# T1_Card_Top.net
KiCad netlist of a schematic drawn in Altium Designer
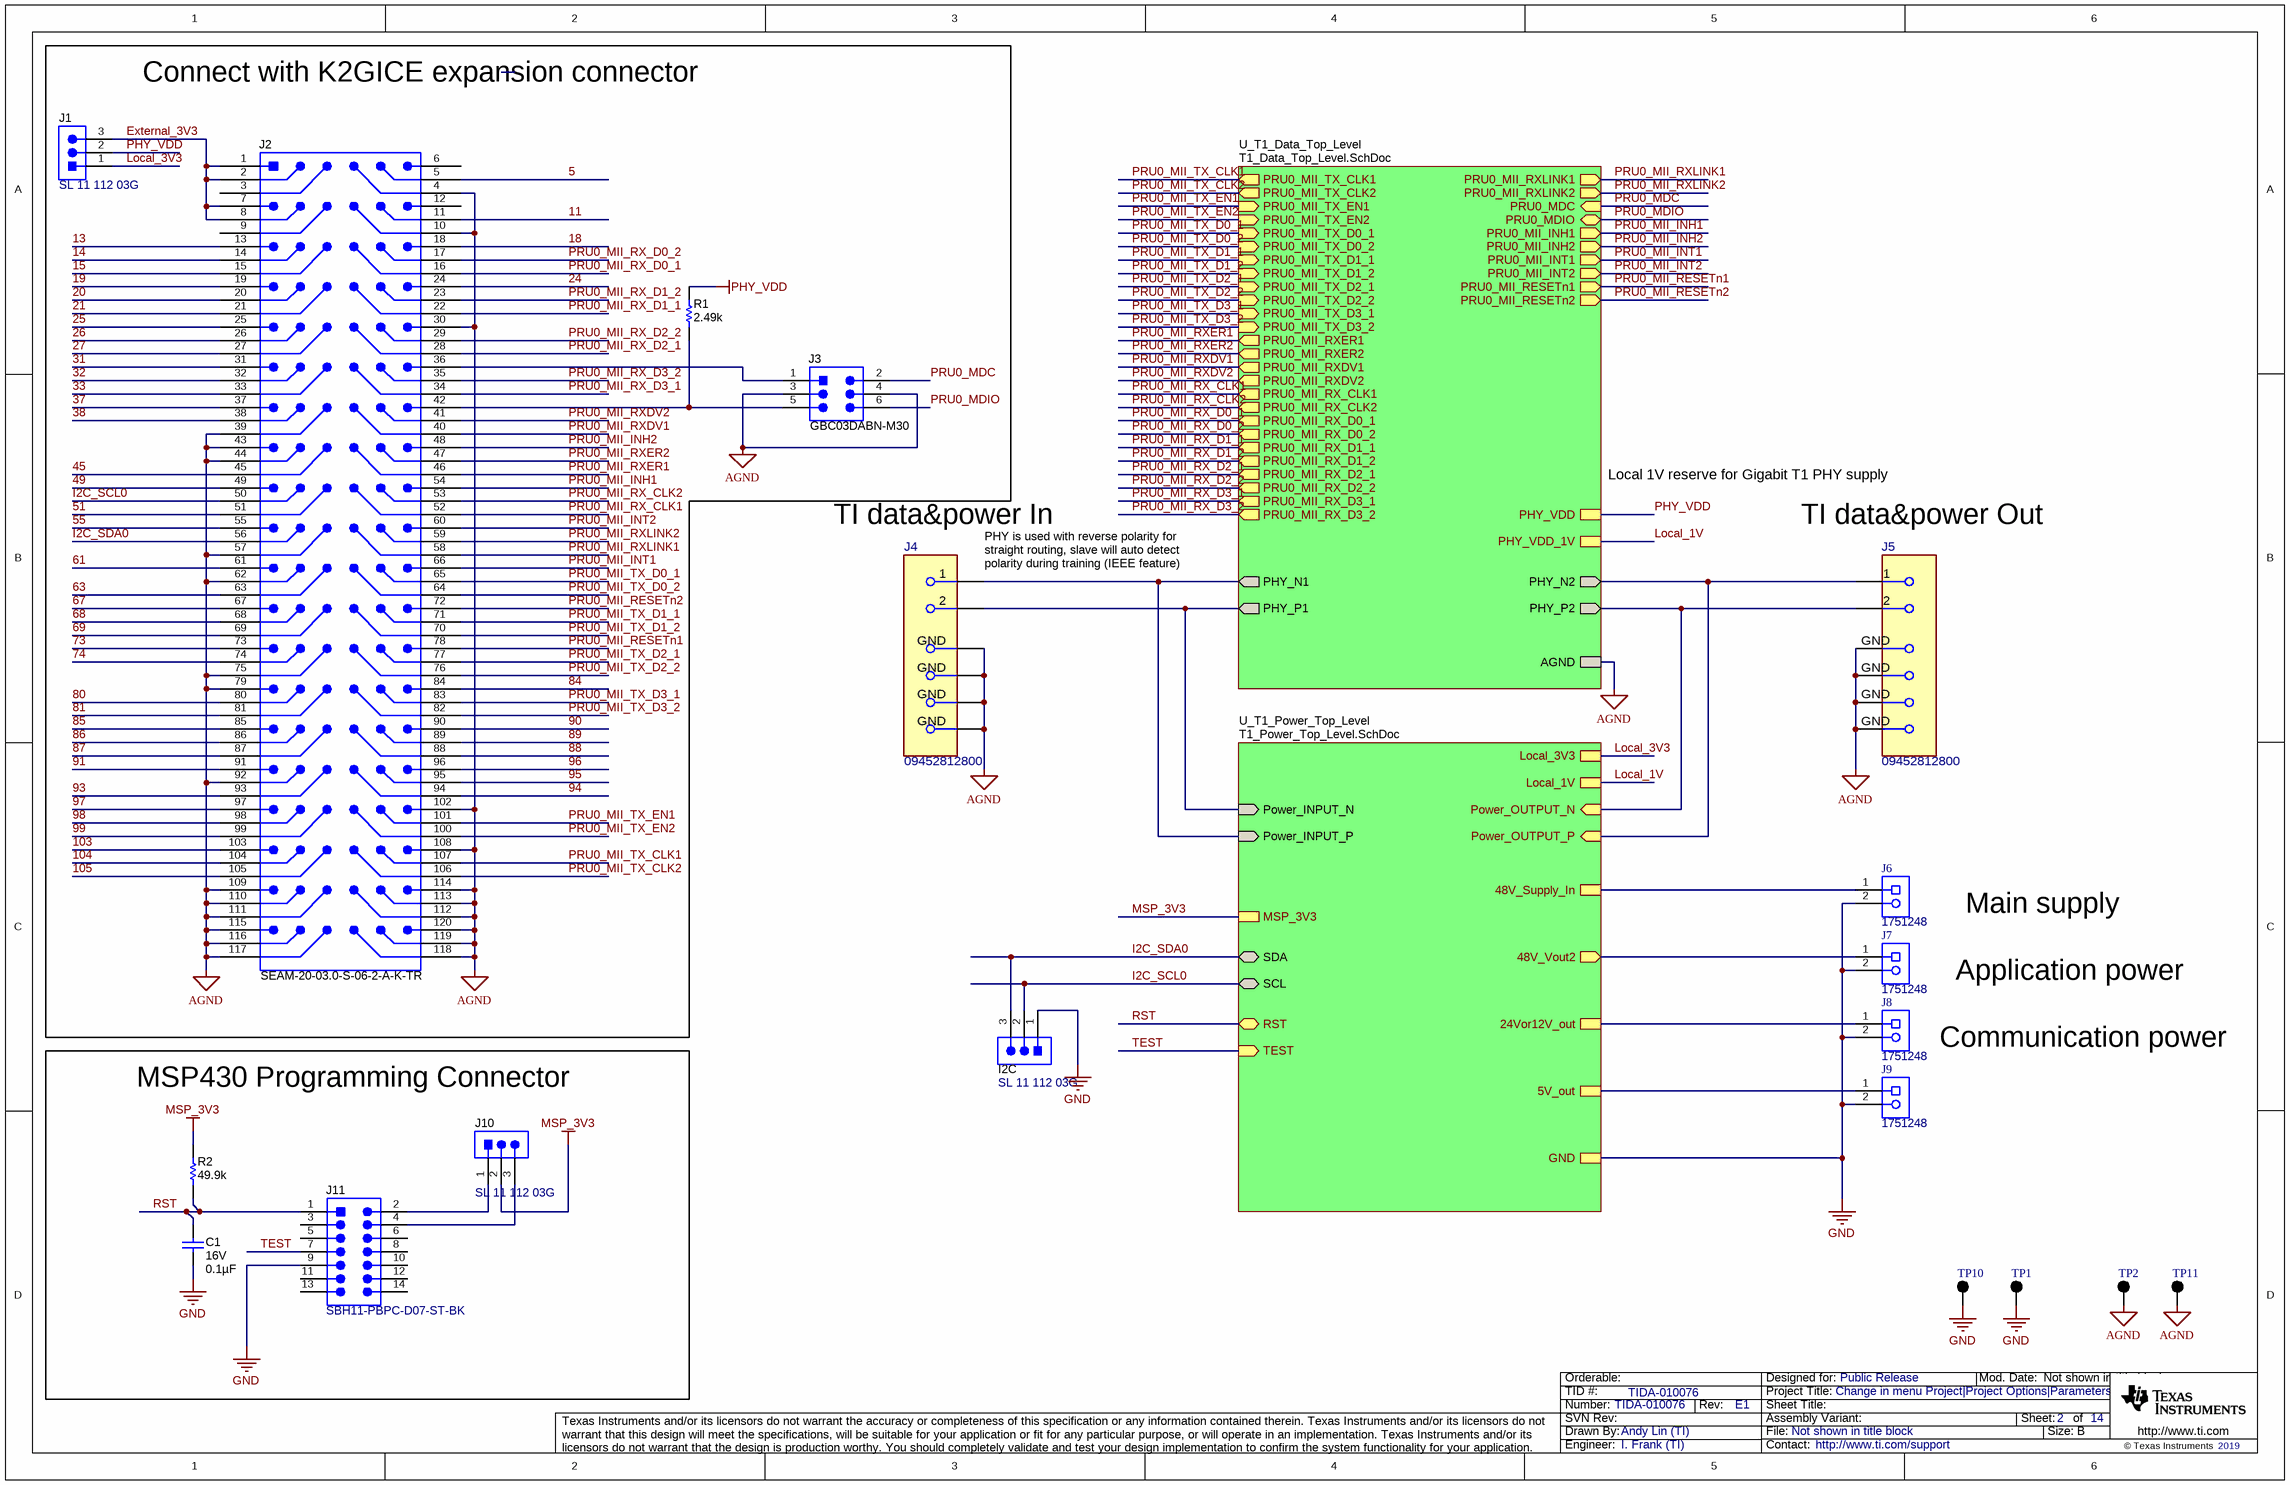
[diagram p0: T1_Card_Top.SchDoc]

(export (version "E")
  (design (tool "Eeschema 10.0.6"))
  (components
    (comp (ref "C1")
      (value "GCM155R71C104JA55D")
      (footprint "0402")
      (description "CAP, CERM, 0.1 µF, 16 V,+/- 5%, X7R, AEC-Q200 Grade 1, 0402")
      (fields
        (field (name "MANUFACTURER") "MuRata")
        (field (name "VDC_V") "16V")
        (field (name "VALUEDISPLAYED") "0.1µF")
      )
      (libsource (lib "Altium Vault - TI") (part "Capacitor"))
    )
    (comp (ref "I2C")
      (value "SL 11 112 03G")
      (footprint "Fischer_SL-11-112-03G")
      (description "Header, 2.54mm, 3x1, Gold, TH")
      (fields
        (field (name "MANUFACTURER") "Fischer Elektronik")
        (field (name "PUBLISHER") "Texas Instruments")
      )
      (libsource (lib "") (part "Header_3x1_2"))
    )
    (comp (ref "J1")
      (value "SL 11 112 03G")
      (footprint "Fischer_SL-11-112-03G")
      (description "Header, 2.54mm, 3x1, Gold, TH")
      (fields
        (field (name "MANUFACTURER") "Fischer Elektronik")
        (field (name "PUBLISHER") "Texas Instruments")
      )
      (libsource (lib "") (part "Header_3x1_1"))
    )
    (comp (ref "J2")
      (value "SEAM-20-03.0-S-06-2-A-K-TR")
      (footprint "Samtec_SEAM-20-03_0-x-06-2-A-K")
      (description "Header(shrouded), 1.27mm, 20x6, Gold, SMT")
      (fields (field (name "MANUFACTURER") "Samtec") (field (name "PUBLISHER") "Texas Instruments"))
      (libsource (lib "Altium Vault - TI") (part "Header_20x6"))
    )
    (comp (ref "J3")
      (value "GBC03DABN-M30")
      (footprint "Sullins_GBC03DABN-M30")
      (description "Header, 2.54mm, 3x2, Gold, Black, SMT")
      (fields (field (name "MANUFACTURER") "Sullins Connector Solutions"))
      (libsource (lib "Altium Vault - TI") (part "Header_3x2"))
    )
    (comp (ref "J4")
      (value "09452812800")
      (footprint "FP-09452812800_HDR2-MFG")
      (description "T1 Industrial jack AH IP20")
      (fields (field (name "MANUFACTURER") "Harting Electronics"))
      (libsource (lib "") (part "SYM-09452812800_1"))
    )
    (comp (ref "J5")
      (value "09452812800")
      (footprint "FP-09452812800_HDR2-MFG")
      (description "T1 Industrial jack AH IP20")
      (fields (field (name "MANUFACTURER") "Harting Electronics"))
      (libsource (lib "Altium Vault - TI") (part "SYM-09452812800"))
    )
    (comp (ref "J6")
      (value "1751248")
      (footprint "CONN_1751248")
      (description "Conn Term Block, 2POS, 3.5mm, TH")
      (fields (field (name "MANUFACTURER") "Phoenix Contact") (field (name "PUBLISHER") "Texas Instruments"))
      (libsource (lib "Altium Vault - TI") (part "Receptacle_2x1"))
    )
    (comp (ref "J7")
      (value "1751248")
      (footprint "CONN_1751248")
      (description "Conn Term Block, 2POS, 3.5mm, TH")
      (fields (field (name "MANUFACTURER") "Phoenix Contact") (field (name "PUBLISHER") "Texas Instruments"))
      (libsource (lib "Altium Vault - TI") (part "Receptacle_2x1"))
    )
    (comp (ref "J8")
      (value "1751248")
      (footprint "CONN_1751248")
      (description "Conn Term Block, 2POS, 3.5mm, TH")
      (fields (field (name "MANUFACTURER") "Phoenix Contact") (field (name "PUBLISHER") "Texas Instruments"))
      (libsource (lib "Altium Vault - TI") (part "Receptacle_2x1"))
    )
    (comp (ref "J9")
      (value "1751248")
      (footprint "CONN_1751248")
      (description "Conn Term Block, 2POS, 3.5mm, TH")
      (fields (field (name "MANUFACTURER") "Phoenix Contact") (field (name "PUBLISHER") "Texas Instruments"))
      (libsource (lib "Altium Vault - TI") (part "Receptacle_2x1"))
    )
    (comp (ref "J10")
      (value "SL 11 112 03G")
      (footprint "Fischer_SL-11-112-03G")
      (description "Header, 2.54mm, 3x1, Gold, TH")
      (fields
        (field (name "MANUFACTURER") "Fischer Elektronik")
        (field (name "PUBLISHER") "Texas Instruments")
      )
      (libsource (lib "Altium Vault - TI") (part "Header_3x1"))
    )
    (comp (ref "J11")
      (value "SBH11-PBPC-D07-ST-BK")
      (footprint "CONN_SBH11-PBPC-D07-ST-BK")
      (description "Header (shrouded), 100 mil, 7x2, Gold, TH")
      (fields (field (name "MANUFACTURER") "Sullins Connector Solutions"))
      (libsource (lib "Altium Vault - TI") (part "Header_7x2"))
    )
    (comp (ref "R1")
      (value "CRCW04022K49FKED")
      (footprint "0402")
      (description "RES, 2.49 k, 1%, 0.063 W, AEC-Q200 Grade 0, 0402")
      (fields (field (name "MANUFACTURER") "Vishay-Dale") (field (name "VALUEDISPLAYED") "2.49k"))
      (libsource (lib "Altium Vault - TI") (part "Resistor"))
    )
    (comp (ref "R2")
      (value "CRCW040249K9FKED")
      (footprint "0402")
      (description "RES, 49.9 k, 1%, 0.063 W, AEC-Q200 Grade 0, 0402")
      (fields (field (name "MANUFACTURER") "Vishay-Dale") (field (name "VALUEDISPLAYED") "49.9k"))
      (libsource (lib "Altium Vault - TI") (part "Resistor"))
    )
    (comp (ref "TP1")
      (value "5001")
      (footprint "Keystone5001")
      (description "Test Point, Miniature, Black, TH")
      (fields (field (name "MANUFACTURER") "Keystone") (field (name "PUBLISHER") "Texas Instruments"))
      (libsource (lib "Altium Vault - TI") (part "5001"))
    )
    (comp (ref "TP2")
      (value "5001")
      (footprint "Keystone5001")
      (description "Test Point, Miniature, Black, TH")
      (fields (field (name "MANUFACTURER") "Keystone") (field (name "PUBLISHER") "Texas Instruments"))
      (libsource (lib "Altium Vault - TI") (part "5001"))
    )
    (comp (ref "TP10")
      (value "5001")
      (footprint "Keystone5001")
      (description "Test Point, Miniature, Black, TH")
      (fields (field (name "MANUFACTURER") "Keystone") (field (name "PUBLISHER") "Texas Instruments"))
      (libsource (lib "Altium Vault - TI") (part "5001"))
    )
    (comp (ref "TP11")
      (value "5001")
      (footprint "Keystone5001")
      (description "Test Point, Miniature, Black, TH")
      (fields (field (name "MANUFACTURER") "Keystone") (field (name "PUBLISHER") "Texas Instruments"))
      (libsource (lib "Altium Vault - TI") (part "5001"))
    )
  )
  (nets
    (net (code "1") (name "/5") (class "Default")
      (node (ref "J2") (pin "5") (pinfunction "5_5") (pintype "passive"))
    )
    (net (code "2") (name "/5V_out") (class "Default")
      (node (ref "J9") (pin "1") (pinfunction "1_1") (pintype "passive"))
    )
    (net (code "3") (name "/11") (class "Default")
      (node (ref "J2") (pin "11") (pinfunction "11_11") (pintype "passive"))
    )
    (net (code "4") (name "/13") (class "Default")
      (node (ref "J2") (pin "13") (pinfunction "13_13") (pintype "passive"))
    )
    (net (code "5") (name "/14") (class "Default")
      (node (ref "J2") (pin "14") (pinfunction "14_14") (pintype "passive"))
    )
    (net (code "6") (name "/15") (class "Default")
      (node (ref "J2") (pin "15") (pinfunction "15_15") (pintype "passive"))
    )
    (net (code "7") (name "/18") (class "Default")
      (node (ref "J2") (pin "18") (pinfunction "18_18") (pintype "passive"))
    )
    (net (code "8") (name "/19") (class "Default")
      (node (ref "J2") (pin "19") (pinfunction "19_19") (pintype "passive"))
    )
    (net (code "9") (name "/20") (class "Default")
      (node (ref "J2") (pin "20") (pinfunction "20_20") (pintype "passive"))
    )
    (net (code "10") (name "/21") (class "Default")
      (node (ref "J2") (pin "21") (pinfunction "21_21") (pintype "passive"))
    )
    (net (code "11") (name "/24") (class "Default")
      (node (ref "J2") (pin "24") (pinfunction "24_24") (pintype "passive"))
    )
    (net (code "12") (name "/24Vor12V_out") (class "Default")
      (node (ref "J8") (pin "1") (pinfunction "1_1") (pintype "passive"))
    )
    (net (code "13") (name "/25") (class "Default")
      (node (ref "J2") (pin "25") (pinfunction "25_25") (pintype "passive"))
    )
    (net (code "14") (name "/26") (class "Default")
      (node (ref "J2") (pin "26") (pinfunction "26_26") (pintype "passive"))
    )
    (net (code "15") (name "/27") (class "Default")
      (node (ref "J2") (pin "27") (pinfunction "27_27") (pintype "passive"))
    )
    (net (code "16") (name "/31") (class "Default")
      (node (ref "J2") (pin "31") (pinfunction "31_31") (pintype "passive"))
    )
    (net (code "17") (name "/32") (class "Default")
      (node (ref "J2") (pin "32") (pinfunction "32_32") (pintype "passive"))
    )
    (net (code "18") (name "/33") (class "Default")
      (node (ref "J2") (pin "33") (pinfunction "33_33") (pintype "passive"))
    )
    (net (code "19") (name "/37") (class "Default")
      (node (ref "J2") (pin "37") (pinfunction "37_37") (pintype "passive"))
    )
    (net (code "20") (name "/38") (class "Default")
      (node (ref "J2") (pin "38") (pinfunction "38_38") (pintype "passive"))
    )
    (net (code "21") (name "/45") (class "Default")
      (node (ref "J2") (pin "45") (pinfunction "45_45") (pintype "passive"))
    )
    (net (code "22") (name "/48V_Supply_In") (class "Default")
      (node (ref "J6") (pin "1") (pinfunction "1_1") (pintype "passive"))
    )
    (net (code "23") (name "/48V_Vout2") (class "Default")
      (node (ref "J7") (pin "1") (pinfunction "1_1") (pintype "passive"))
    )
    (net (code "24") (name "/49") (class "Default")
      (node (ref "J2") (pin "49") (pinfunction "49_49") (pintype "passive"))
    )
    (net (code "25") (name "/51") (class "Default")
      (node (ref "J2") (pin "51") (pinfunction "51_51") (pintype "passive"))
    )
    (net (code "26") (name "/55") (class "Default")
      (node (ref "J2") (pin "55") (pinfunction "55_55") (pintype "passive"))
    )
    (net (code "27") (name "/61") (class "Default")
      (node (ref "J2") (pin "61") (pinfunction "61_61") (pintype "passive"))
    )
    (net (code "28") (name "/63") (class "Default")
      (node (ref "J2") (pin "63") (pinfunction "63_63") (pintype "passive"))
    )
    (net (code "29") (name "/67") (class "Default")
      (node (ref "J2") (pin "67") (pinfunction "67_67") (pintype "passive"))
    )
    (net (code "30") (name "/68") (class "Default")
      (node (ref "J2") (pin "68") (pinfunction "68_68") (pintype "passive"))
    )
    (net (code "31") (name "/69") (class "Default")
      (node (ref "J2") (pin "69") (pinfunction "69_69") (pintype "passive"))
    )
    (net (code "32") (name "/73") (class "Default")
      (node (ref "J2") (pin "73") (pinfunction "73_73") (pintype "passive"))
    )
    (net (code "33") (name "/74") (class "Default")
      (node (ref "J2") (pin "74") (pinfunction "74_74") (pintype "passive"))
    )
    (net (code "34") (name "/80") (class "Default")
      (node (ref "J2") (pin "80") (pinfunction "80_80") (pintype "passive"))
    )
    (net (code "35") (name "/81") (class "Default")
      (node (ref "J2") (pin "81") (pinfunction "81_81") (pintype "passive"))
    )
    (net (code "36") (name "/84") (class "Default")
      (node (ref "J2") (pin "84") (pinfunction "84_84") (pintype "passive"))
    )
    (net (code "37") (name "/85") (class "Default")
      (node (ref "J2") (pin "85") (pinfunction "85_85") (pintype "passive"))
    )
    (net (code "38") (name "/86") (class "Default")
      (node (ref "J2") (pin "86") (pinfunction "86_86") (pintype "passive"))
    )
    (net (code "39") (name "/87") (class "Default")
      (node (ref "J2") (pin "87") (pinfunction "87_87") (pintype "passive"))
    )
    (net (code "40") (name "/88") (class "Default")
      (node (ref "J2") (pin "88") (pinfunction "88_88") (pintype "passive"))
    )
    (net (code "41") (name "/89") (class "Default")
      (node (ref "J2") (pin "89") (pinfunction "89_89") (pintype "passive"))
    )
    (net (code "42") (name "/90") (class "Default")
      (node (ref "J2") (pin "90") (pinfunction "90_90") (pintype "passive"))
    )
    (net (code "43") (name "/91") (class "Default")
      (node (ref "J2") (pin "91") (pinfunction "91_91") (pintype "passive"))
    )
    (net (code "44") (name "/93") (class "Default")
      (node (ref "J2") (pin "93") (pinfunction "93_93") (pintype "passive"))
    )
    (net (code "45") (name "/94") (class "Default")
      (node (ref "J2") (pin "94") (pinfunction "94_94") (pintype "passive"))
    )
    (net (code "46") (name "/95") (class "Default")
      (node (ref "J2") (pin "95") (pinfunction "95_95") (pintype "passive"))
    )
    (net (code "47") (name "/96") (class "Default")
      (node (ref "J2") (pin "96") (pinfunction "96_96") (pintype "passive"))
    )
    (net (code "48") (name "/97") (class "Default")
      (node (ref "J2") (pin "97") (pinfunction "97_97") (pintype "passive"))
    )
    (net (code "49") (name "/98") (class "Default")
      (node (ref "J2") (pin "98") (pinfunction "98_98") (pintype "passive"))
    )
    (net (code "50") (name "/99") (class "Default")
      (node (ref "J2") (pin "99") (pinfunction "99_99") (pintype "passive"))
    )
    (net (code "51") (name "/103") (class "Default")
      (node (ref "J2") (pin "103") (pinfunction "103_103") (pintype "passive"))
    )
    (net (code "52") (name "/104") (class "Default")
      (node (ref "J2") (pin "104") (pinfunction "104_104") (pintype "passive"))
    )
    (net (code "53") (name "/105") (class "Default")
      (node (ref "J2") (pin "105") (pinfunction "105_105") (pintype "passive"))
    )
    (net (code "54") (name "/External_3V3") (class "Default")
      (node (ref "J1") (pin "3") (pinfunction "3_3") (pintype "passive"))
      (node (ref "J2") (pin "1") (pinfunction "1_1") (pintype "passive"))
      (node (ref "J2") (pin "2") (pinfunction "2_2") (pintype "passive"))
      (node (ref "J2") (pin "7") (pinfunction "7_7") (pintype "passive"))
      (node (ref "J2") (pin "8") (pinfunction "8_8") (pintype "passive"))
    )
    (net (code "55") (name "/I2C_SCL0") (class "Default")
      (node (ref "I2C") (pin "2") (pinfunction "2_2") (pintype "passive"))
      (node (ref "J2") (pin "50") (pinfunction "50_50") (pintype "passive"))
    )
    (net (code "56") (name "/I2C_SDA0") (class "Default")
      (node (ref "I2C") (pin "3") (pinfunction "3_3") (pintype "passive"))
      (node (ref "J2") (pin "56") (pinfunction "56_56") (pintype "passive"))
    )
    (net (code "58") (name "/Local_3V3") (class "Default")
      (node (ref "J1") (pin "1") (pinfunction "1_1") (pintype "passive"))
    )
    (net (code "59") (name "/PHY_N1") (class "Default")
      (node (ref "J4") (pin "1") (pinfunction "1_1") (pintype "passive"))
    )
    (net (code "60") (name "/PHY_N2") (class "Default")
      (node (ref "J5") (pin "1") (pinfunction "1_1") (pintype "passive"))
    )
    (net (code "61") (name "/PHY_P1") (class "Default")
      (node (ref "J4") (pin "2") (pinfunction "2_2") (pintype "passive"))
    )
    (net (code "62") (name "/PHY_P2") (class "Default")
      (node (ref "J5") (pin "2") (pinfunction "2_2") (pintype "passive"))
    )
    (net (code "63") (name "/PRU0_MDC") (class "Default")
      (node (ref "J3") (pin "2") (pinfunction "2_2") (pintype "passive"))
    )
    (net (code "64") (name "/PRU0_MDIO") (class "Default")
      (node (ref "J3") (pin "6") (pinfunction "6_6") (pintype "passive"))
    )
    (net (code "65") (name "/PRU0_MII_INH1") (class "Default")
      (node (ref "J2") (pin "54") (pinfunction "54_54") (pintype "passive"))
    )
    (net (code "66") (name "/PRU0_MII_INH2") (class "Default")
      (node (ref "J2") (pin "48") (pinfunction "48_48") (pintype "passive"))
    )
    (net (code "67") (name "/PRU0_MII_INT1") (class "Default")
      (node (ref "J2") (pin "66") (pinfunction "66_66") (pintype "passive"))
    )
    (net (code "68") (name "/PRU0_MII_INT2") (class "Default")
      (node (ref "J2") (pin "60") (pinfunction "60_60") (pintype "passive"))
    )
    (net (code "69") (name "/PRU0_MII_RESETn1") (class "Default")
      (node (ref "J2") (pin "78") (pinfunction "78_78") (pintype "passive"))
    )
    (net (code "70") (name "/PRU0_MII_RESETn2") (class "Default")
      (node (ref "J2") (pin "72") (pinfunction "72_72") (pintype "passive"))
    )
    (net (code "71") (name "/PRU0_MII_RXDV1") (class "Default")
      (node (ref "J2") (pin "40") (pinfunction "40_40") (pintype "passive"))
    )
    (net (code "72") (name "/PRU0_MII_RXDV2") (class "Default")
      (node (ref "J2") (pin "41") (pinfunction "41_41") (pintype "passive"))
    )
    (net (code "73") (name "/PRU0_MII_RXER1") (class "Default")
      (node (ref "J2") (pin "46") (pinfunction "46_46") (pintype "passive"))
    )
    (net (code "74") (name "/PRU0_MII_RXER2") (class "Default")
      (node (ref "J2") (pin "47") (pinfunction "47_47") (pintype "passive"))
    )
    (net (code "75") (name "/PRU0_MII_RXLINK1") (class "Default")
      (node (ref "J2") (pin "58") (pinfunction "58_58") (pintype "passive"))
    )
    (net (code "76") (name "/PRU0_MII_RXLINK2") (class "Default")
      (node (ref "J2") (pin "59") (pinfunction "59_59") (pintype "passive"))
    )
    (net (code "77") (name "/PRU0_MII_RX_CLK1") (class "Default")
      (node (ref "J2") (pin "52") (pinfunction "52_52") (pintype "passive"))
    )
    (net (code "78") (name "/PRU0_MII_RX_CLK2") (class "Default")
      (node (ref "J2") (pin "53") (pinfunction "53_53") (pintype "passive"))
    )
    (net (code "79") (name "/PRU0_MII_RX_D0_1") (class "Default")
      (node (ref "J2") (pin "16") (pinfunction "16_16") (pintype "passive"))
    )
    (net (code "80") (name "/PRU0_MII_RX_D0_2") (class "Default")
      (node (ref "J2") (pin "17") (pinfunction "17_17") (pintype "passive"))
    )
    (net (code "81") (name "/PRU0_MII_RX_D1_1") (class "Default")
      (node (ref "J2") (pin "22") (pinfunction "22_22") (pintype "passive"))
    )
    (net (code "82") (name "/PRU0_MII_RX_D1_2") (class "Default")
      (node (ref "J2") (pin "23") (pinfunction "23_23") (pintype "passive"))
    )
    (net (code "83") (name "/PRU0_MII_RX_D2_1") (class "Default")
      (node (ref "J2") (pin "28") (pinfunction "28_28") (pintype "passive"))
    )
    (net (code "84") (name "/PRU0_MII_RX_D2_2") (class "Default")
      (node (ref "J2") (pin "29") (pinfunction "29_29") (pintype "passive"))
    )
    (net (code "85") (name "/PRU0_MII_RX_D3_1") (class "Default")
      (node (ref "J2") (pin "34") (pinfunction "34_34") (pintype "passive"))
    )
    (net (code "86") (name "/PRU0_MII_RX_D3_2") (class "Default")
      (node (ref "J2") (pin "35") (pinfunction "35_35") (pintype "passive"))
    )
    (net (code "87") (name "/PRU0_MII_TX_CLK1") (class "Default")
      (node (ref "J2") (pin "107") (pinfunction "107_107") (pintype "passive"))
    )
    (net (code "88") (name "/PRU0_MII_TX_CLK2") (class "Default")
      (node (ref "J2") (pin "106") (pinfunction "106_106") (pintype "passive"))
    )
    (net (code "89") (name "/PRU0_MII_TX_D0_1") (class "Default")
      (node (ref "J2") (pin "65") (pinfunction "65_65") (pintype "passive"))
    )
    (net (code "90") (name "/PRU0_MII_TX_D0_2") (class "Default")
      (node (ref "J2") (pin "64") (pinfunction "64_64") (pintype "passive"))
    )
    (net (code "91") (name "/PRU0_MII_TX_D1_1") (class "Default")
      (node (ref "J2") (pin "71") (pinfunction "71_71") (pintype "passive"))
    )
    (net (code "92") (name "/PRU0_MII_TX_D1_2") (class "Default")
      (node (ref "J2") (pin "70") (pinfunction "70_70") (pintype "passive"))
    )
    (net (code "93") (name "/PRU0_MII_TX_D2_1") (class "Default")
      (node (ref "J2") (pin "77") (pinfunction "77_77") (pintype "passive"))
    )
    (net (code "94") (name "/PRU0_MII_TX_D2_2") (class "Default")
      (node (ref "J2") (pin "76") (pinfunction "76_76") (pintype "passive"))
    )
    (net (code "95") (name "/PRU0_MII_TX_D3_1") (class "Default")
      (node (ref "J2") (pin "83") (pinfunction "83_83") (pintype "passive"))
    )
    (net (code "96") (name "/PRU0_MII_TX_D3_2") (class "Default")
      (node (ref "J2") (pin "82") (pinfunction "82_82") (pintype "passive"))
    )
    (net (code "97") (name "/PRU0_MII_TX_EN1") (class "Default")
      (node (ref "J2") (pin "101") (pinfunction "101_101") (pintype "passive"))
    )
    (net (code "98") (name "/PRU0_MII_TX_EN2") (class "Default")
      (node (ref "J2") (pin "100") (pinfunction "100_100") (pintype "passive"))
    )
    (net (code "99") (name "/RST") (class "Default")
      (node (ref "C1") (pin "1") (pinfunction "1_1") (pintype "passive"))
      (node (ref "J11") (pin "1") (pinfunction "1_1") (pintype "passive"))
      (node (ref "R2") (pin "1") (pinfunction "1_1") (pintype "passive"))
    )
    (net (code "100") (name "/TEST") (class "Default")
      (node (ref "J11") (pin "7") (pinfunction "7_7") (pintype "passive"))
    )
    (net (code "101") (name "AGND") (class "Default")
      (node (ref "J2") (pin "10") (pinfunction "10_10") (pintype "passive"))
      (node (ref "J2") (pin "102") (pinfunction "102_102") (pintype "passive"))
      (node (ref "J2") (pin "108") (pinfunction "108_108") (pintype "passive"))
      (node (ref "J2") (pin "109") (pinfunction "109_109") (pintype "passive"))
      (node (ref "J2") (pin "110") (pinfunction "110_110") (pintype "passive"))
      (node (ref "J2") (pin "111") (pinfunction "111_111") (pintype "passive"))
      (node (ref "J2") (pin "112") (pinfunction "112_112") (pintype "passive"))
      (node (ref "J2") (pin "113") (pinfunction "113_113") (pintype "passive"))
      (node (ref "J2") (pin "114") (pinfunction "114_114") (pintype "passive"))
      (node (ref "J2") (pin "115") (pinfunction "115_115") (pintype "passive"))
      (node (ref "J2") (pin "116") (pinfunction "116_116") (pintype "passive"))
      (node (ref "J2") (pin "117") (pinfunction "117_117") (pintype "passive"))
      (node (ref "J2") (pin "118") (pinfunction "118_118") (pintype "passive"))
      (node (ref "J2") (pin "119") (pinfunction "119_119") (pintype "passive"))
      (node (ref "J2") (pin "120") (pinfunction "120_120") (pintype "passive"))
      (node (ref "J2") (pin "30") (pinfunction "30_30") (pintype "passive"))
      (node (ref "J2") (pin "39") (pinfunction "39_39") (pintype "passive"))
      (node (ref "J2") (pin "4") (pinfunction "4_4") (pintype "passive"))
      (node (ref "J2") (pin "43") (pinfunction "43_43") (pintype "passive"))
      (node (ref "J2") (pin "44") (pinfunction "44_44") (pintype "passive"))
      (node (ref "J2") (pin "57") (pinfunction "57_57") (pintype "passive"))
      (node (ref "J2") (pin "62") (pinfunction "62_62") (pintype "passive"))
      (node (ref "J2") (pin "75") (pinfunction "75_75") (pintype "passive"))
      (node (ref "J2") (pin "79") (pinfunction "79_79") (pintype "passive"))
      (node (ref "J2") (pin "92") (pinfunction "92_92") (pintype "passive"))
      (node (ref "J3") (pin "3") (pinfunction "3_3") (pintype "passive"))
      (node (ref "J3") (pin "4") (pinfunction "4_4") (pintype "passive"))
      (node (ref "J4") (pin "3") (pinfunction "GND_3") (pintype "power_in"))
      (node (ref "J4") (pin "4") (pinfunction "GND_4") (pintype "power_in"))
      (node (ref "J4") (pin "5") (pinfunction "GND_5") (pintype "power_in"))
      (node (ref "J4") (pin "6") (pinfunction "GND_6") (pintype "power_in"))
      (node (ref "J5") (pin "3") (pinfunction "GND_3") (pintype "power_in"))
      (node (ref "J5") (pin "4") (pinfunction "GND_4") (pintype "power_in"))
      (node (ref "J5") (pin "5") (pinfunction "GND_5") (pintype "power_in"))
      (node (ref "J5") (pin "6") (pinfunction "GND_6") (pintype "power_in"))
      (node (ref "TP11") (pin "1") (pintype "passive"))
      (node (ref "TP2") (pin "1") (pintype "passive"))
    )
    (net (code "102") (name "GND") (class "Default")
      (node (ref "C1") (pin "2") (pinfunction "2_2") (pintype "passive"))
      (node (ref "I2C") (pin "1") (pinfunction "1_1") (pintype "passive"))
      (node (ref "J11") (pin "9") (pinfunction "9_9") (pintype "passive"))
      (node (ref "J6") (pin "2") (pinfunction "2_2") (pintype "passive"))
      (node (ref "J7") (pin "2") (pinfunction "2_2") (pintype "passive"))
      (node (ref "J8") (pin "2") (pinfunction "2_2") (pintype "passive"))
      (node (ref "J9") (pin "2") (pinfunction "2_2") (pintype "passive"))
      (node (ref "TP1") (pin "1") (pintype "passive"))
      (node (ref "TP10") (pin "1") (pintype "passive"))
    )
    (net (code "103") (name "MSP_3V3") (class "Default")
      (node (ref "J10") (pin "2") (pinfunction "2_2") (pintype "passive"))
      (node (ref "R2") (pin "2") (pinfunction "2_2") (pintype "passive"))
    )
    (net (code "104") (name "Net-(J2-Pad36)") (class "Default")
      (node (ref "J2") (pin "36") (pinfunction "36_36") (pintype "passive"))
      (node (ref "J3") (pin "1") (pinfunction "1_1") (pintype "passive"))
    )
    (net (code "105") (name "Net-(J2-Pad42)") (class "Default")
      (node (ref "J2") (pin "42") (pinfunction "42_42") (pintype "passive"))
      (node (ref "J3") (pin "5") (pinfunction "5_5") (pintype "passive"))
      (node (ref "R1") (pin "1") (pinfunction "1_1") (pintype "passive"))
    )
    (net (code "106") (name "Net-(J10-Pad1)") (class "Default")
      (node (ref "J10") (pin "1") (pinfunction "1_1") (pintype "passive"))
      (node (ref "J11") (pin "2") (pinfunction "2_2") (pintype "passive"))
    )
    (net (code "107") (name "Net-(J10-Pad3)") (class "Default")
      (node (ref "J10") (pin "3") (pinfunction "3_3") (pintype "passive"))
      (node (ref "J11") (pin "4") (pinfunction "4_4") (pintype "passive"))
    )
    (net (code "108") (name "PHY_VDD") (class "Default")
      (node (ref "J1") (pin "2") (pinfunction "2_2") (pintype "passive"))
      (node (ref "R1") (pin "2") (pinfunction "2_2") (pintype "passive"))
    )
    (net (code "109") (name "unconnected-(J2-Pad3)") (class "Default")
      (node (ref "J2") (pin "3") (pinfunction "3_3") (pintype "passive"))
    )
    (net (code "110") (name "unconnected-(J2-Pad6)") (class "Default")
      (node (ref "J2") (pin "6") (pinfunction "6_6") (pintype "passive"))
    )
    (net (code "111") (name "unconnected-(J2-Pad9)") (class "Default")
      (node (ref "J2") (pin "9") (pinfunction "9_9") (pintype "passive"))
    )
    (net (code "112") (name "unconnected-(J2-Pad12)") (class "Default")
      (node (ref "J2") (pin "12") (pinfunction "12_12") (pintype "passive"))
    )
    (net (code "113") (name "unconnected-(J11-Pad3)") (class "Default")
      (node (ref "J11") (pin "3") (pinfunction "3_3") (pintype "passive"))
    )
    (net (code "114") (name "unconnected-(J11-Pad5)") (class "Default")
      (node (ref "J11") (pin "5") (pinfunction "5_5") (pintype "passive"))
    )
    (net (code "115") (name "unconnected-(J11-Pad6)") (class "Default")
      (node (ref "J11") (pin "6") (pinfunction "6_6") (pintype "passive"))
    )
    (net (code "116") (name "unconnected-(J11-Pad8)") (class "Default")
      (node (ref "J11") (pin "8") (pinfunction "8_8") (pintype "passive"))
    )
    (net (code "117") (name "unconnected-(J11-Pad10)") (class "Default")
      (node (ref "J11") (pin "10") (pinfunction "10_10") (pintype "passive"))
    )
    (net (code "118") (name "unconnected-(J11-Pad11)") (class "Default")
      (node (ref "J11") (pin "11") (pinfunction "11_11") (pintype "passive"))
    )
    (net (code "119") (name "unconnected-(J11-Pad12)") (class "Default")
      (node (ref "J11") (pin "12") (pinfunction "12_12") (pintype "passive"))
    )
    (net (code "120") (name "unconnected-(J11-Pad13)") (class "Default")
      (node (ref "J11") (pin "13") (pinfunction "13_13") (pintype "passive"))
    )
    (net (code "121") (name "unconnected-(J11-Pad14)") (class "Default")
      (node (ref "J11") (pin "14") (pinfunction "14_14") (pintype "passive"))
    )
  )
)
